# AC-4ch-01.net
KiCad netlist of a schematic drawn in EAGLE
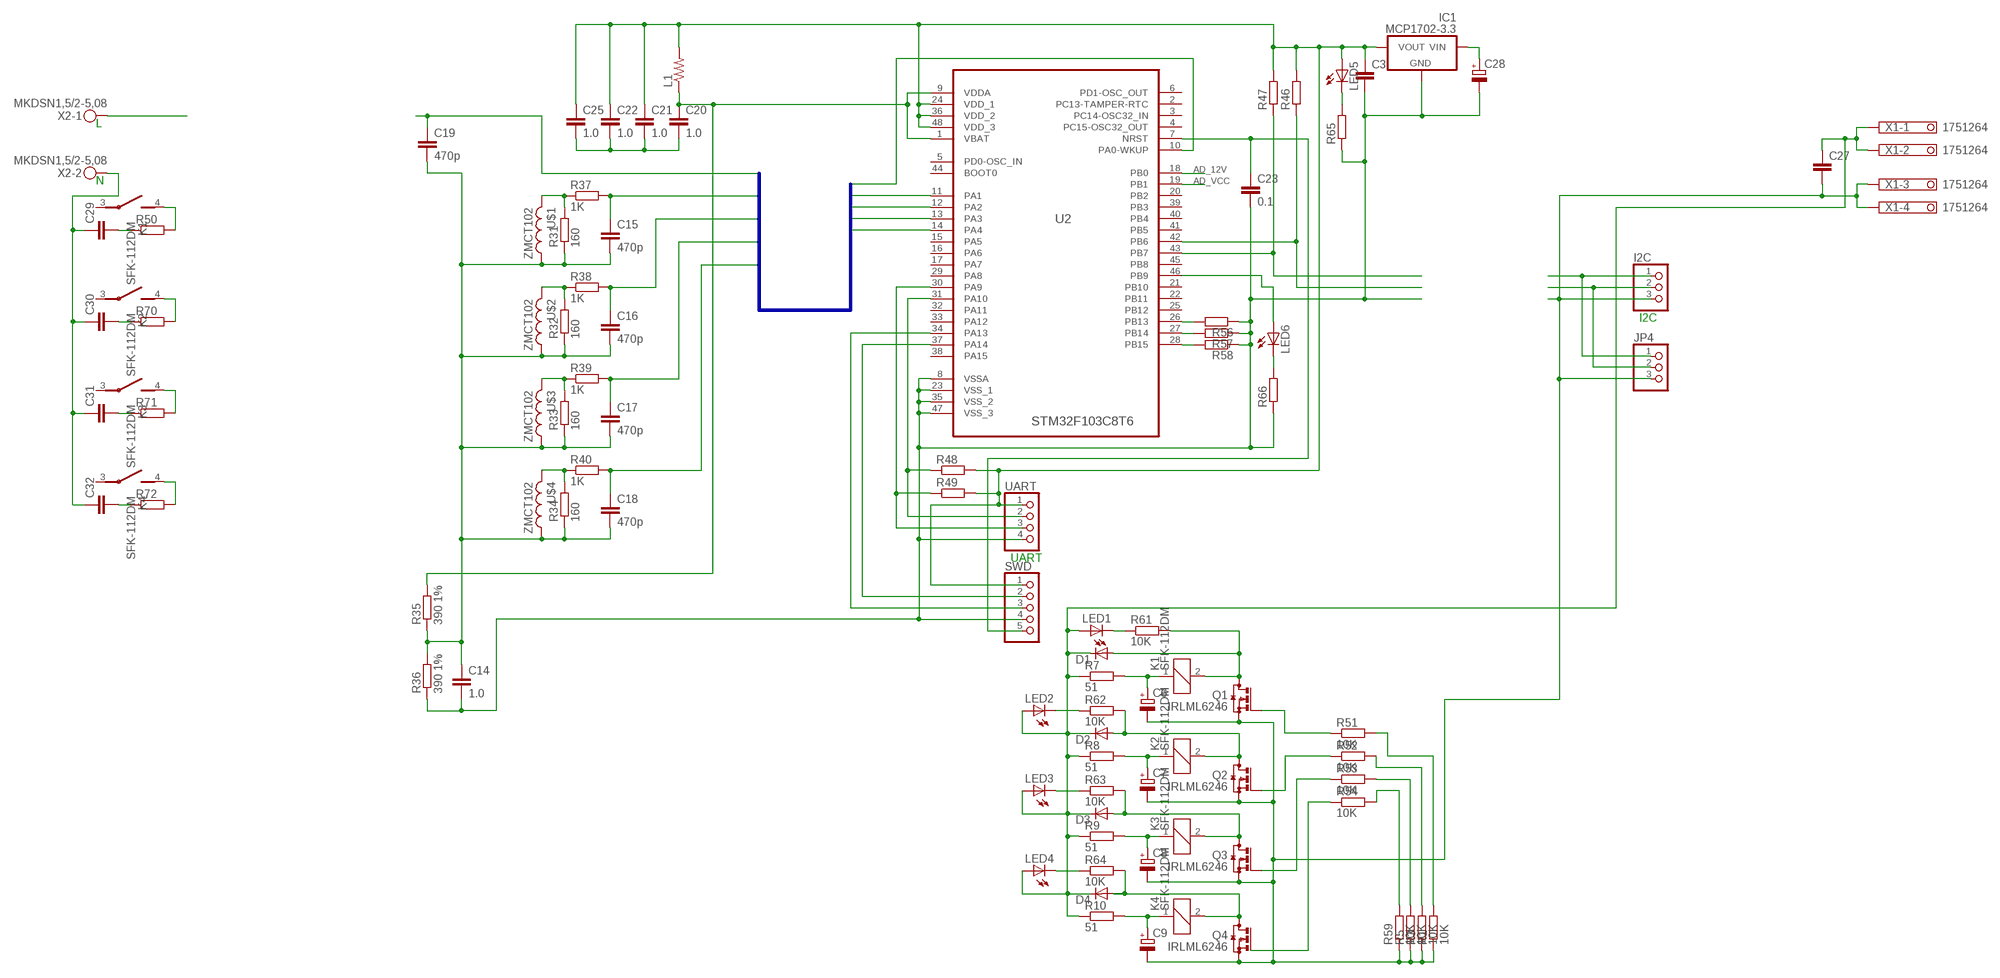
[diagram p0: schematic, sheet 1]

(export (version "E")
  (design (tool "Eeschema 10.0.6"))
  (components
    (comp (ref "C3")
      (value "C-EUC0805")
      (footprint "eagle-import:C0805")
      (libsource (lib "eagle-import") (part "C-EUC0805"))
    )
    (comp (ref "C6")
      (value "CPOL-EUE3.5-8")
      (footprint "eagle-import:E3,5-8")
      (libsource (lib "eagle-import") (part "CPOL-EUE3.5-8"))
    )
    (comp (ref "C7")
      (value "CPOL-EUE3.5-8")
      (footprint "eagle-import:E3,5-8")
      (libsource (lib "eagle-import") (part "CPOL-EUE3.5-8"))
    )
    (comp (ref "C8")
      (value "CPOL-EUE3.5-8")
      (footprint "eagle-import:E3,5-8")
      (libsource (lib "eagle-import") (part "CPOL-EUE3.5-8"))
    )
    (comp (ref "C9")
      (value "CPOL-EUE3.5-8")
      (footprint "eagle-import:E3,5-8")
      (libsource (lib "eagle-import") (part "CPOL-EUE3.5-8"))
    )
    (comp (ref "C14")
      (value "1.0")
      (footprint "eagle-import:C0805")
      (libsource (lib "eagle-import") (part "C-EUC0805"))
    )
    (comp (ref "C15")
      (value "470p")
      (footprint "eagle-import:C0603")
      (libsource (lib "eagle-import") (part "C-EUC0603"))
    )
    (comp (ref "C16")
      (value "470p")
      (footprint "eagle-import:C0603")
      (libsource (lib "eagle-import") (part "C-EUC0603"))
    )
    (comp (ref "C17")
      (value "470p")
      (footprint "eagle-import:C0603")
      (libsource (lib "eagle-import") (part "C-EUC0603"))
    )
    (comp (ref "C18")
      (value "470p")
      (footprint "eagle-import:C0603")
      (libsource (lib "eagle-import") (part "C-EUC0603"))
    )
    (comp (ref "C19")
      (value "470p")
      (footprint "eagle-import:C0603")
      (libsource (lib "eagle-import") (part "C-EUC0603"))
    )
    (comp (ref "C20")
      (value "1.0")
      (footprint "eagle-import:C0805")
      (libsource (lib "eagle-import") (part "C-EUC0805"))
    )
    (comp (ref "C21")
      (value "1.0")
      (footprint "eagle-import:C0805")
      (libsource (lib "eagle-import") (part "C-EUC0805"))
    )
    (comp (ref "C22")
      (value "1.0")
      (footprint "eagle-import:C0805")
      (libsource (lib "eagle-import") (part "C-EUC0805"))
    )
    (comp (ref "C23")
      (value "0.1")
      (footprint "eagle-import:C0603")
      (libsource (lib "eagle-import") (part "C-EUC0603"))
    )
    (comp (ref "C25")
      (value "1.0")
      (footprint "eagle-import:C0805")
      (libsource (lib "eagle-import") (part "C-EUC0805"))
    )
    (comp (ref "C27")
      (value "C-EUC1206")
      (footprint "eagle-import:C1206")
      (libsource (lib "eagle-import") (part "C-EUC1206"))
    )
    (comp (ref "C28")
      (value "CPOL-EUSMCB")
      (footprint "eagle-import:SMC_B")
      (libsource (lib "eagle-import") (part "CPOL-EUSMCB"))
    )
    (comp (ref "C29")
      (value "C-EU225-087X268")
      (footprint "eagle-import:C225-087X268")
      (libsource (lib "eagle-import") (part "C-EU225-087X268"))
    )
    (comp (ref "C30")
      (value "C-EU225-087X268")
      (footprint "eagle-import:C225-087X268")
      (libsource (lib "eagle-import") (part "C-EU225-087X268"))
    )
    (comp (ref "C31")
      (value "C-EU225-087X268")
      (footprint "eagle-import:C225-087X268")
      (libsource (lib "eagle-import") (part "C-EU225-087X268"))
    )
    (comp (ref "C32")
      (value "C-EU225-087X268")
      (footprint "eagle-import:C225-087X268")
      (libsource (lib "eagle-import") (part "C-EU225-087X268"))
    )
    (comp (ref "D1")
      (value "DIODE-SOD123")
      (footprint "eagle-import:SOD123")
      (libsource (lib "eagle-import") (part "DIODE-SOD123"))
    )
    (comp (ref "D2")
      (value "DIODE-SOD123")
      (footprint "eagle-import:SOD123")
      (libsource (lib "eagle-import") (part "DIODE-SOD123"))
    )
    (comp (ref "D3")
      (value "DIODE-SOD123")
      (footprint "eagle-import:SOD123")
      (libsource (lib "eagle-import") (part "DIODE-SOD123"))
    )
    (comp (ref "D4")
      (value "DIODE-SOD123")
      (footprint "eagle-import:SOD123")
      (libsource (lib "eagle-import") (part "DIODE-SOD123"))
    )
    (comp (ref "I2C")
      (value "PINHD-1X3")
      (footprint "eagle-import:1X03")
      (libsource (lib "eagle-import") (part "PINHD-1X3"))
    )
    (comp (ref "IC1")
      (value "MCP1702-3.3")
      (footprint "eagle-import:SOT23-3-ROTATED")
      (libsource (lib "eagle-import") (part "MCP1702SOT23"))
    )
    (comp (ref "JP4")
      (value "PINHD-1X3")
      (footprint "eagle-import:1X03")
      (libsource (lib "eagle-import") (part "PINHD-1X3"))
    )
    (comp (ref "K1")
      (value "SFK-112DM")
      (footprint "eagle-import:SFK112")
      (libsource (lib "eagle-import") (part "SFK-112DM"))
    )
    (comp (ref "K2")
      (value "SFK-112DM")
      (footprint "eagle-import:SFK112")
      (libsource (lib "eagle-import") (part "SFK-112DM"))
    )
    (comp (ref "K3")
      (value "SFK-112DM")
      (footprint "eagle-import:SFK112")
      (libsource (lib "eagle-import") (part "SFK-112DM"))
    )
    (comp (ref "K4")
      (value "SFK-112DM")
      (footprint "eagle-import:SFK112")
      (libsource (lib "eagle-import") (part "SFK-112DM"))
    )
    (comp (ref "L1")
      (value "R-US_M0805")
      (footprint "eagle-import:M0805")
      (libsource (lib "eagle-import") (part "R-US_M0805"))
    )
    (comp (ref "LED1")
      (value "LEDCHIP-LED0805")
      (footprint "eagle-import:CHIP-LED0805")
      (libsource (lib "eagle-import") (part "LEDCHIP-LED0805"))
    )
    (comp (ref "LED2")
      (value "LEDCHIP-LED0805")
      (footprint "eagle-import:CHIP-LED0805")
      (libsource (lib "eagle-import") (part "LEDCHIP-LED0805"))
    )
    (comp (ref "LED3")
      (value "LEDCHIP-LED0805")
      (footprint "eagle-import:CHIP-LED0805")
      (libsource (lib "eagle-import") (part "LEDCHIP-LED0805"))
    )
    (comp (ref "LED4")
      (value "LEDCHIP-LED0805")
      (footprint "eagle-import:CHIP-LED0805")
      (libsource (lib "eagle-import") (part "LEDCHIP-LED0805"))
    )
    (comp (ref "LED5")
      (value "LEDCHIP-LED0805")
      (footprint "eagle-import:CHIP-LED0805")
      (libsource (lib "eagle-import") (part "LEDCHIP-LED0805"))
    )
    (comp (ref "LED6")
      (value "LEDCHIP-LED0805")
      (footprint "eagle-import:CHIP-LED0805")
      (libsource (lib "eagle-import") (part "LEDCHIP-LED0805"))
    )
    (comp (ref "Q1")
      (value "IRLML6246")
      (footprint "eagle-import:SOT23")
      (libsource (lib "eagle-import") (part "BSS123"))
    )
    (comp (ref "Q2")
      (value "IRLML6246")
      (footprint "eagle-import:SOT23")
      (libsource (lib "eagle-import") (part "BSS123"))
    )
    (comp (ref "Q3")
      (value "IRLML6246")
      (footprint "eagle-import:SOT23")
      (libsource (lib "eagle-import") (part "BSS123"))
    )
    (comp (ref "Q4")
      (value "IRLML6246")
      (footprint "eagle-import:SOT23")
      (libsource (lib "eagle-import") (part "BSS123"))
    )
    (comp (ref "R1")
      (value "10K")
      (footprint "eagle-import:R0603")
      (libsource (lib "eagle-import") (part "R-EU_R0603"))
    )
    (comp (ref "R3")
      (value "10K")
      (footprint "eagle-import:R0603")
      (libsource (lib "eagle-import") (part "R-EU_R0603"))
    )
    (comp (ref "R5")
      (value "10K")
      (footprint "eagle-import:R0603")
      (libsource (lib "eagle-import") (part "R-EU_R0603"))
    )
    (comp (ref "R7")
      (value "51")
      (footprint "eagle-import:R1206")
      (libsource (lib "eagle-import") (part "R-EU_R1206"))
    )
    (comp (ref "R8")
      (value "51")
      (footprint "eagle-import:R1206")
      (libsource (lib "eagle-import") (part "R-EU_R1206"))
    )
    (comp (ref "R9")
      (value "51")
      (footprint "eagle-import:R1206")
      (libsource (lib "eagle-import") (part "R-EU_R1206"))
    )
    (comp (ref "R10")
      (value "51")
      (footprint "eagle-import:R1206")
      (libsource (lib "eagle-import") (part "R-EU_R1206"))
    )
    (comp (ref "R31")
      (value "160")
      (footprint "eagle-import:R0603")
      (libsource (lib "eagle-import") (part "R-EU_R0603"))
    )
    (comp (ref "R32")
      (value "160")
      (footprint "eagle-import:R0603")
      (libsource (lib "eagle-import") (part "R-EU_R0603"))
    )
    (comp (ref "R33")
      (value "160")
      (footprint "eagle-import:R0603")
      (libsource (lib "eagle-import") (part "R-EU_R0603"))
    )
    (comp (ref "R34")
      (value "160")
      (footprint "eagle-import:R0603")
      (libsource (lib "eagle-import") (part "R-EU_R0603"))
    )
    (comp (ref "R35")
      (value "390 1%")
      (footprint "eagle-import:R0603")
      (libsource (lib "eagle-import") (part "R-EU_R0603"))
    )
    (comp (ref "R36")
      (value "390 1%")
      (footprint "eagle-import:R0603")
      (libsource (lib "eagle-import") (part "R-EU_R0603"))
    )
    (comp (ref "R37")
      (value "1K")
      (footprint "eagle-import:R0603")
      (libsource (lib "eagle-import") (part "R-EU_R0603"))
    )
    (comp (ref "R38")
      (value "1K")
      (footprint "eagle-import:R0603")
      (libsource (lib "eagle-import") (part "R-EU_R0603"))
    )
    (comp (ref "R39")
      (value "1K")
      (footprint "eagle-import:R0603")
      (libsource (lib "eagle-import") (part "R-EU_R0603"))
    )
    (comp (ref "R40")
      (value "1K")
      (footprint "eagle-import:R0603")
      (libsource (lib "eagle-import") (part "R-EU_R0603"))
    )
    (comp (ref "R46")
      (value "R-EU_R0603")
      (footprint "eagle-import:R0603")
      (libsource (lib "eagle-import") (part "R-EU_R0603"))
    )
    (comp (ref "R47")
      (value "R-EU_R0603")
      (footprint "eagle-import:R0603")
      (libsource (lib "eagle-import") (part "R-EU_R0603"))
    )
    (comp (ref "R48")
      (value "R-EU_R0603")
      (footprint "eagle-import:R0603")
      (libsource (lib "eagle-import") (part "R-EU_R0603"))
    )
    (comp (ref "R49")
      (value "R-EU_R0603")
      (footprint "eagle-import:R0603")
      (libsource (lib "eagle-import") (part "R-EU_R0603"))
    )
    (comp (ref "R50")
      (value "R-EU_0414/5V")
      (footprint "eagle-import:0414V")
      (libsource (lib "eagle-import") (part "R-EU_0414/5V"))
    )
    (comp (ref "R51")
      (value "10K")
      (footprint "eagle-import:R0603")
      (libsource (lib "eagle-import") (part "R-EU_R0603"))
    )
    (comp (ref "R52")
      (value "10K")
      (footprint "eagle-import:R0603")
      (libsource (lib "eagle-import") (part "R-EU_R0603"))
    )
    (comp (ref "R53")
      (value "10K")
      (footprint "eagle-import:R0603")
      (libsource (lib "eagle-import") (part "R-EU_R0603"))
    )
    (comp (ref "R54")
      (value "10K")
      (footprint "eagle-import:R0603")
      (libsource (lib "eagle-import") (part "R-EU_R0603"))
    )
    (comp (ref "R56")
      (value "R-EU_R0603")
      (footprint "eagle-import:R0603")
      (libsource (lib "eagle-import") (part "R-EU_R0603"))
    )
    (comp (ref "R57")
      (value "R-EU_R0603")
      (footprint "eagle-import:R0603")
      (libsource (lib "eagle-import") (part "R-EU_R0603"))
    )
    (comp (ref "R58")
      (value "R-EU_R0603")
      (footprint "eagle-import:R0603")
      (libsource (lib "eagle-import") (part "R-EU_R0603"))
    )
    (comp (ref "R59")
      (value "10K")
      (footprint "eagle-import:R0603")
      (libsource (lib "eagle-import") (part "R-EU_R0603"))
    )
    (comp (ref "R61")
      (value "10K")
      (footprint "eagle-import:R0603")
      (libsource (lib "eagle-import") (part "R-EU_R0603"))
    )
    (comp (ref "R62")
      (value "10K")
      (footprint "eagle-import:R0603")
      (libsource (lib "eagle-import") (part "R-EU_R0603"))
    )
    (comp (ref "R63")
      (value "10K")
      (footprint "eagle-import:R0603")
      (libsource (lib "eagle-import") (part "R-EU_R0603"))
    )
    (comp (ref "R64")
      (value "10K")
      (footprint "eagle-import:R0603")
      (libsource (lib "eagle-import") (part "R-EU_R0603"))
    )
    (comp (ref "R65")
      (value "R-EU_R0603")
      (footprint "eagle-import:R0603")
      (libsource (lib "eagle-import") (part "R-EU_R0603"))
    )
    (comp (ref "R66")
      (value "R-EU_R0603")
      (footprint "eagle-import:R0603")
      (libsource (lib "eagle-import") (part "R-EU_R0603"))
    )
    (comp (ref "R70")
      (value "R-EU_0414/5V")
      (footprint "eagle-import:0414V")
      (libsource (lib "eagle-import") (part "R-EU_0414/5V"))
    )
    (comp (ref "R71")
      (value "R-EU_0414/5V")
      (footprint "eagle-import:0414V")
      (libsource (lib "eagle-import") (part "R-EU_0414/5V"))
    )
    (comp (ref "R72")
      (value "R-EU_0414/5V")
      (footprint "eagle-import:0414V")
      (libsource (lib "eagle-import") (part "R-EU_0414/5V"))
    )
    (comp (ref "SWD")
      (value "PINHD-1X5")
      (footprint "eagle-import:1X05")
      (libsource (lib "eagle-import") (part "PINHD-1X5"))
    )
    (comp (ref "U$1")
      (value "ZMCT102")
      (footprint "eagle-import:ZMCT")
      (libsource (lib "eagle-import") (part "ZMCT102"))
    )
    (comp (ref "U$2")
      (value "ZMCT102")
      (footprint "eagle-import:ZMCT")
      (libsource (lib "eagle-import") (part "ZMCT102"))
    )
    (comp (ref "U$3")
      (value "ZMCT102")
      (footprint "eagle-import:ZMCT")
      (libsource (lib "eagle-import") (part "ZMCT102"))
    )
    (comp (ref "U$4")
      (value "ZMCT102")
      (footprint "eagle-import:ZMCT")
      (libsource (lib "eagle-import") (part "ZMCT102"))
    )
    (comp (ref "U2")
      (value "STM32F103C8T6")
      (footprint "eagle-import:QFP50P900X900X160-48N")
      (fields (field (name "MPN") "STM32F100CBT6B"))
      (libsource (lib "eagle-import") (part "STM32F100CBT6B"))
    )
    (comp (ref "UART")
      (value "PINHD-1X4")
      (footprint "eagle-import:1X04")
      (libsource (lib "eagle-import") (part "PINHD-1X4"))
    )
    (comp (ref "X1")
      (value "1751264")
      (footprint "eagle-import:1751264")
      (libsource (lib "eagle-import") (part "1751264"))
    )
    (comp (ref "X2")
      (value "MKDSN1,5/2-5,08")
      (footprint "eagle-import:MKDSN1,5_2-5,08")
      (libsource (lib "eagle-import") (part "MKDSN1,5/2-5,08"))
    )
  )
  (nets
    (net (code "1") (name "/0V") (class "Default")
      (node (ref "C14") (pin "2") (pinfunction "2_2") (pintype "passive"))
      (node (ref "C20") (pin "2") (pinfunction "2_2") (pintype "passive"))
      (node (ref "C21") (pin "2") (pinfunction "2_2") (pintype "passive"))
      (node (ref "C22") (pin "2") (pinfunction "2_2") (pintype "passive"))
      (node (ref "C23") (pin "2") (pinfunction "2_2") (pintype "passive"))
      (node (ref "C25") (pin "2") (pinfunction "2_2") (pintype "passive"))
      (node (ref "C28") (pin "-") (pinfunction "-_-") (pintype "passive"))
      (node (ref "C3") (pin "2") (pinfunction "2_2") (pintype "passive"))
      (node (ref "IC1") (pin "1") (pinfunction "GND_1") (pintype "passive"))
      (node (ref "R36") (pin "1") (pinfunction "1_1") (pintype "passive"))
      (node (ref "R56") (pin "1") (pinfunction "1_1") (pintype "passive"))
      (node (ref "R57") (pin "1") (pinfunction "1_1") (pintype "passive"))
      (node (ref "R58") (pin "1") (pinfunction "1_1") (pintype "passive"))
      (node (ref "R65") (pin "1") (pinfunction "1_1") (pintype "passive"))
      (node (ref "R66") (pin "1") (pinfunction "1_1") (pintype "passive"))
      (node (ref "SWD") (pin "4") (pinfunction "4_4") (pintype "passive"))
      (node (ref "U2") (pin "23") (pinfunction "VSS_1_23") (pintype "power_in"))
      (node (ref "U2") (pin "35") (pinfunction "VSS_2_35") (pintype "power_in"))
      (node (ref "U2") (pin "47") (pinfunction "VSS_3_47") (pintype "power_in"))
      (node (ref "U2") (pin "8") (pinfunction "VSSA_8") (pintype "power_in"))
      (node (ref "UART") (pin "4") (pinfunction "4_4") (pintype "passive"))
    )
    (net (code "2") (name "/A0") (class "Default")
      (node (ref "C18") (pin "1") (pinfunction "1_1") (pintype "passive"))
      (node (ref "R40") (pin "2") (pinfunction "2_2") (pintype "passive"))
      (node (ref "U2") (pin "10") (pinfunction "PA0-WKUP_10") (pintype "bidirectional"))
    )
    (net (code "3") (name "/A1") (class "Default")
      (node (ref "C17") (pin "1") (pinfunction "1_1") (pintype "passive"))
      (node (ref "R39") (pin "2") (pinfunction "2_2") (pintype "passive"))
      (node (ref "U2") (pin "11") (pinfunction "PA1_11") (pintype "bidirectional"))
    )
    (net (code "4") (name "/A2") (class "Default")
      (node (ref "C16") (pin "1") (pinfunction "1_1") (pintype "passive"))
      (node (ref "R38") (pin "2") (pinfunction "2_2") (pintype "passive"))
      (node (ref "U2") (pin "12") (pinfunction "PA2_12") (pintype "bidirectional"))
    )
    (net (code "5") (name "/A3") (class "Default")
      (node (ref "C15") (pin "1") (pinfunction "1_1") (pintype "passive"))
      (node (ref "R37") (pin "2") (pinfunction "2_2") (pintype "passive"))
      (node (ref "U2") (pin "13") (pinfunction "PA3_13") (pintype "bidirectional"))
    )
    (net (code "6") (name "/A4") (class "Default")
      (node (ref "C19") (pin "1") (pinfunction "1_1") (pintype "passive"))
      (node (ref "U2") (pin "14") (pinfunction "PA4_14") (pintype "bidirectional"))
    )
    (net (code "7") (name "/AD_12V") (class "Default")
      (node (ref "U2") (pin "18") (pinfunction "PB0_18") (pintype "bidirectional"))
    )
    (net (code "8") (name "/AD_VCC") (class "Default")
      (node (ref "U2") (pin "19") (pinfunction "PB1_19") (pintype "bidirectional"))
    )
    (net (code "9") (name "Net-(C6-Pad+)") (class "Default")
      (node (ref "C6") (pin "+") (pinfunction "+_+") (pintype "passive"))
      (node (ref "K1") (pin "1") (pinfunction "1_1") (pintype "passive"))
      (node (ref "R7") (pin "2") (pinfunction "2_2") (pintype "passive"))
    )
    (net (code "10") (name "Net-(C7-Pad+)") (class "Default")
      (node (ref "C7") (pin "+") (pinfunction "+_+") (pintype "passive"))
      (node (ref "K2") (pin "1") (pinfunction "1_1") (pintype "passive"))
      (node (ref "R8") (pin "2") (pinfunction "2_2") (pintype "passive"))
    )
    (net (code "11") (name "Net-(C8-Pad+)") (class "Default")
      (node (ref "C8") (pin "+") (pinfunction "+_+") (pintype "passive"))
      (node (ref "K3") (pin "1") (pinfunction "1_1") (pintype "passive"))
      (node (ref "R9") (pin "2") (pinfunction "2_2") (pintype "passive"))
    )
    (net (code "12") (name "Net-(C9-Pad+)") (class "Default")
      (node (ref "C9") (pin "+") (pinfunction "+_+") (pintype "passive"))
      (node (ref "K4") (pin "1") (pinfunction "1_1") (pintype "passive"))
      (node (ref "R10") (pin "2") (pinfunction "2_2") (pintype "passive"))
    )
    (net (code "13") (name "Net-(C14-Pad1)") (class "Default")
      (node (ref "C14") (pin "1") (pinfunction "1_1") (pintype "passive"))
      (node (ref "C15") (pin "2") (pinfunction "2_2") (pintype "passive"))
      (node (ref "C16") (pin "2") (pinfunction "2_2") (pintype "passive"))
      (node (ref "C17") (pin "2") (pinfunction "2_2") (pintype "passive"))
      (node (ref "C18") (pin "2") (pinfunction "2_2") (pintype "passive"))
      (node (ref "C19") (pin "2") (pinfunction "2_2") (pintype "passive"))
      (node (ref "R31") (pin "1") (pinfunction "1_1") (pintype "passive"))
      (node (ref "R32") (pin "1") (pinfunction "1_1") (pintype "passive"))
      (node (ref "R33") (pin "1") (pinfunction "1_1") (pintype "passive"))
      (node (ref "R34") (pin "1") (pinfunction "1_1") (pintype "passive"))
      (node (ref "R35") (pin "1") (pinfunction "1_1") (pintype "passive"))
      (node (ref "R36") (pin "2") (pinfunction "2_2") (pintype "passive"))
      (node (ref "U$1") (pin "1") (pinfunction "1_1") (pintype "passive"))
      (node (ref "U$2") (pin "1") (pinfunction "1_1") (pintype "passive"))
      (node (ref "U$3") (pin "1") (pinfunction "1_1") (pintype "passive"))
      (node (ref "U$4") (pin "1") (pinfunction "1_1") (pintype "passive"))
    )
    (net (code "14") (name "Net-(C29-Pad2)") (class "Default")
      (node (ref "C29") (pin "2") (pinfunction "2_2") (pintype "passive"))
      (node (ref "R50") (pin "1") (pinfunction "1_1") (pintype "passive"))
    )
    (net (code "15") (name "Net-(C30-Pad2)") (class "Default")
      (node (ref "C30") (pin "2") (pinfunction "2_2") (pintype "passive"))
      (node (ref "R70") (pin "1") (pinfunction "1_1") (pintype "passive"))
    )
    (net (code "16") (name "Net-(C31-Pad2)") (class "Default")
      (node (ref "C31") (pin "2") (pinfunction "2_2") (pintype "passive"))
      (node (ref "R71") (pin "1") (pinfunction "1_1") (pintype "passive"))
    )
    (net (code "17") (name "Net-(C32-Pad2)") (class "Default")
      (node (ref "C32") (pin "2") (pinfunction "2_2") (pintype "passive"))
      (node (ref "R72") (pin "1") (pinfunction "1_1") (pintype "passive"))
    )
    (net (code "18") (name "Net-(I2C-Pad1)") (class "Default")
      (node (ref "I2C") (pin "1") (pinfunction "1_1") (pintype "passive"))
      (node (ref "JP4") (pin "1") (pinfunction "1_1") (pintype "passive"))
    )
    (net (code "19") (name "Net-(I2C-Pad2)") (class "Default")
      (node (ref "I2C") (pin "2") (pinfunction "2_2") (pintype "passive"))
      (node (ref "JP4") (pin "2") (pinfunction "2_2") (pintype "passive"))
    )
    (net (code "20") (name "Net-(IC1-VIN)") (class "Default")
      (node (ref "C28") (pin "+") (pinfunction "+_+") (pintype "passive"))
      (node (ref "IC1") (pin "3") (pinfunction "VIN_3") (pintype "input"))
    )
    (net (code "21") (name "Net-(IC1-VOUT)") (class "Default")
      (node (ref "C21") (pin "1") (pinfunction "1_1") (pintype "passive"))
      (node (ref "C22") (pin "1") (pinfunction "1_1") (pintype "passive"))
      (node (ref "C25") (pin "1") (pinfunction "1_1") (pintype "passive"))
      (node (ref "C3") (pin "1") (pinfunction "1_1") (pintype "passive"))
      (node (ref "IC1") (pin "2") (pinfunction "VOUT_2") (pintype "passive"))
      (node (ref "L1") (pin "2") (pinfunction "2_2") (pintype "passive"))
      (node (ref "LED5") (pin "A") (pinfunction "A_A") (pintype "passive"))
      (node (ref "R46") (pin "2") (pinfunction "2_2") (pintype "passive"))
      (node (ref "R47") (pin "2") (pinfunction "2_2") (pintype "passive"))
      (node (ref "R48") (pin "2") (pinfunction "2_2") (pintype "passive"))
      (node (ref "R49") (pin "2") (pinfunction "2_2") (pintype "passive"))
      (node (ref "SWD") (pin "1") (pinfunction "1_1") (pintype "passive"))
      (node (ref "U2") (pin "24") (pinfunction "VDD_1_24") (pintype "power_in"))
      (node (ref "U2") (pin "36") (pinfunction "VDD_2_36") (pintype "power_in"))
      (node (ref "U2") (pin "48") (pinfunction "VDD_3_48") (pintype "power_in"))
      (node (ref "UART") (pin "1") (pinfunction "1_1") (pintype "passive"))
    )
    (net (code "22") (name "Net-(K1A-S)") (class "Default")
      (node (ref "K1") (pin "4") (pinfunction "S_4") (pintype "passive"))
      (node (ref "R50") (pin "2") (pinfunction "2_2") (pintype "passive"))
    )
    (net (code "23") (name "Net-(K2A-S)") (class "Default")
      (node (ref "K2") (pin "4") (pinfunction "S_4") (pintype "passive"))
      (node (ref "R70") (pin "2") (pinfunction "2_2") (pintype "passive"))
    )
    (net (code "24") (name "Net-(K3A-S)") (class "Default")
      (node (ref "K3") (pin "4") (pinfunction "S_4") (pintype "passive"))
      (node (ref "R71") (pin "2") (pinfunction "2_2") (pintype "passive"))
    )
    (net (code "25") (name "Net-(K4A-S)") (class "Default")
      (node (ref "K4") (pin "4") (pinfunction "S_4") (pintype "passive"))
      (node (ref "R72") (pin "2") (pinfunction "2_2") (pintype "passive"))
    )
    (net (code "26") (name "Net-(LED1-PadC)") (class "Default")
      (node (ref "LED1") (pin "C") (pinfunction "C_C") (pintype "passive"))
      (node (ref "R61") (pin "1") (pinfunction "1_1") (pintype "passive"))
    )
    (net (code "27") (name "Net-(LED2-PadC)") (class "Default")
      (node (ref "LED2") (pin "C") (pinfunction "C_C") (pintype "passive"))
      (node (ref "R62") (pin "1") (pinfunction "1_1") (pintype "passive"))
    )
    (net (code "28") (name "Net-(LED3-PadC)") (class "Default")
      (node (ref "LED3") (pin "C") (pinfunction "C_C") (pintype "passive"))
      (node (ref "R63") (pin "1") (pinfunction "1_1") (pintype "passive"))
    )
    (net (code "29") (name "Net-(LED4-PadC)") (class "Default")
      (node (ref "LED4") (pin "C") (pinfunction "C_C") (pintype "passive"))
      (node (ref "R64") (pin "1") (pinfunction "1_1") (pintype "passive"))
    )
    (net (code "30") (name "Net-(LED5-PadC)") (class "Default")
      (node (ref "LED5") (pin "C") (pinfunction "C_C") (pintype "passive"))
      (node (ref "R65") (pin "2") (pinfunction "2_2") (pintype "passive"))
    )
    (net (code "31") (name "Net-(LED6-PadC)") (class "Default")
      (node (ref "LED6") (pin "C") (pinfunction "C_C") (pintype "passive"))
      (node (ref "R66") (pin "2") (pinfunction "2_2") (pintype "passive"))
    )
    (net (code "32") (name "Net-(Q1-D)") (class "Default")
      (node (ref "D1") (pin "A") (pinfunction "A_A") (pintype "passive"))
      (node (ref "K1") (pin "2") (pinfunction "2_2") (pintype "passive"))
      (node (ref "Q1") (pin "3") (pinfunction "D_3") (pintype "passive"))
      (node (ref "R61") (pin "2") (pinfunction "2_2") (pintype "passive"))
    )
    (net (code "33") (name "Net-(Q1-G)") (class "Default")
      (node (ref "Q1") (pin "1") (pinfunction "G_1") (pintype "passive"))
      (node (ref "R51") (pin "1") (pinfunction "1_1") (pintype "passive"))
    )
    (net (code "34") (name "Net-(Q1-S)") (class "Default")
      (node (ref "C27") (pin "2") (pinfunction "2_2") (pintype "passive"))
      (node (ref "C6") (pin "-") (pinfunction "-_-") (pintype "passive"))
      (node (ref "C7") (pin "-") (pinfunction "-_-") (pintype "passive"))
      (node (ref "C8") (pin "-") (pinfunction "-_-") (pintype "passive"))
      (node (ref "C9") (pin "-") (pinfunction "-_-") (pintype "passive"))
      (node (ref "I2C") (pin "3") (pinfunction "3_3") (pintype "passive"))
      (node (ref "JP4") (pin "3") (pinfunction "3_3") (pintype "passive"))
      (node (ref "Q1") (pin "2") (pinfunction "S_2") (pintype "passive"))
      (node (ref "Q2") (pin "2") (pinfunction "S_2") (pintype "passive"))
      (node (ref "Q3") (pin "2") (pinfunction "S_2") (pintype "passive"))
      (node (ref "Q4") (pin "2") (pinfunction "S_2") (pintype "passive"))
      (node (ref "R1") (pin "1") (pinfunction "1_1") (pintype "passive"))
      (node (ref "R3") (pin "1") (pinfunction "1_1") (pintype "passive"))
      (node (ref "R5") (pin "1") (pinfunction "1_1") (pintype "passive"))
      (node (ref "R59") (pin "1") (pinfunction "1_1") (pintype "passive"))
      (node (ref "X1") (pin "3") (pinfunction "K_3") (pintype "passive"))
      (node (ref "X1") (pin "4") (pinfunction "K_4") (pintype "passive"))
    )
    (net (code "35") (name "Net-(Q2-D)") (class "Default")
      (node (ref "D2") (pin "A") (pinfunction "A_A") (pintype "passive"))
      (node (ref "K2") (pin "2") (pinfunction "2_2") (pintype "passive"))
      (node (ref "Q2") (pin "3") (pinfunction "D_3") (pintype "passive"))
      (node (ref "R62") (pin "2") (pinfunction "2_2") (pintype "passive"))
    )
    (net (code "36") (name "Net-(Q2-G)") (class "Default")
      (node (ref "Q2") (pin "1") (pinfunction "G_1") (pintype "passive"))
      (node (ref "R52") (pin "1") (pinfunction "1_1") (pintype "passive"))
    )
    (net (code "37") (name "Net-(Q3-D)") (class "Default")
      (node (ref "D3") (pin "A") (pinfunction "A_A") (pintype "passive"))
      (node (ref "K3") (pin "2") (pinfunction "2_2") (pintype "passive"))
      (node (ref "Q3") (pin "3") (pinfunction "D_3") (pintype "passive"))
      (node (ref "R63") (pin "2") (pinfunction "2_2") (pintype "passive"))
    )
    (net (code "38") (name "Net-(Q3-G)") (class "Default")
      (node (ref "Q3") (pin "1") (pinfunction "G_1") (pintype "passive"))
      (node (ref "R53") (pin "1") (pinfunction "1_1") (pintype "passive"))
    )
    (net (code "39") (name "Net-(Q4-D)") (class "Default")
      (node (ref "D4") (pin "A") (pinfunction "A_A") (pintype "passive"))
      (node (ref "K4") (pin "2") (pinfunction "2_2") (pintype "passive"))
      (node (ref "Q4") (pin "3") (pinfunction "D_3") (pintype "passive"))
      (node (ref "R64") (pin "2") (pinfunction "2_2") (pintype "passive"))
    )
    (net (code "40") (name "Net-(Q4-G)") (class "Default")
      (node (ref "Q4") (pin "1") (pinfunction "G_1") (pintype "passive"))
      (node (ref "R54") (pin "1") (pinfunction "1_1") (pintype "passive"))
    )
    (net (code "41") (name "Net-(R1-Pad2)") (class "Default")
      (node (ref "R1") (pin "2") (pinfunction "2_2") (pintype "passive"))
      (node (ref "R51") (pin "2") (pinfunction "2_2") (pintype "passive"))
    )
    (net (code "42") (name "Net-(R3-Pad2)") (class "Default")
      (node (ref "R3") (pin "2") (pinfunction "2_2") (pintype "passive"))
      (node (ref "R52") (pin "2") (pinfunction "2_2") (pintype "passive"))
    )
    (net (code "43") (name "Net-(R5-Pad2)") (class "Default")
      (node (ref "R5") (pin "2") (pinfunction "2_2") (pintype "passive"))
      (node (ref "R53") (pin "2") (pinfunction "2_2") (pintype "passive"))
    )
    (net (code "44") (name "Net-(R31-Pad2)") (class "Default")
      (node (ref "R31") (pin "2") (pinfunction "2_2") (pintype "passive"))
      (node (ref "R37") (pin "1") (pinfunction "1_1") (pintype "passive"))
      (node (ref "U$1") (pin "2") (pinfunction "2_2") (pintype "passive"))
    )
    (net (code "45") (name "Net-(R32-Pad2)") (class "Default")
      (node (ref "R32") (pin "2") (pinfunction "2_2") (pintype "passive"))
      (node (ref "R38") (pin "1") (pinfunction "1_1") (pintype "passive"))
      (node (ref "U$2") (pin "2") (pinfunction "2_2") (pintype "passive"))
    )
    (net (code "46") (name "Net-(R33-Pad2)") (class "Default")
      (node (ref "R33") (pin "2") (pinfunction "2_2") (pintype "passive"))
      (node (ref "R39") (pin "1") (pinfunction "1_1") (pintype "passive"))
      (node (ref "U$3") (pin "2") (pinfunction "2_2") (pintype "passive"))
    )
    (net (code "47") (name "Net-(R34-Pad2)") (class "Default")
      (node (ref "R34") (pin "2") (pinfunction "2_2") (pintype "passive"))
      (node (ref "R40") (pin "1") (pinfunction "1_1") (pintype "passive"))
      (node (ref "U$4") (pin "2") (pinfunction "2_2") (pintype "passive"))
    )
    (net (code "48") (name "Net-(R54-Pad2)") (class "Default")
      (node (ref "R54") (pin "2") (pinfunction "2_2") (pintype "passive"))
      (node (ref "R59") (pin "2") (pinfunction "2_2") (pintype "passive"))
    )
    (net (code "49") (name "Net-(U2-NRST)") (class "Default")
      (node (ref "C23") (pin "1") (pinfunction "1_1") (pintype "passive"))
      (node (ref "SWD") (pin "5") (pinfunction "5_5") (pintype "passive"))
      (node (ref "U2") (pin "7") (pinfunction "NRST_7") (pintype "bidirectional"))
    )
    (net (code "50") (name "Net-(U2-PA9)") (class "Default")
      (node (ref "R49") (pin "1") (pinfunction "1_1") (pintype "passive"))
      (node (ref "U2") (pin "30") (pinfunction "PA9_30") (pintype "bidirectional"))
      (node (ref "UART") (pin "3") (pinfunction "3_3") (pintype "passive"))
    )
    (net (code "51") (name "Net-(U2-PA10)") (class "Default")
      (node (ref "R48") (pin "1") (pinfunction "1_1") (pintype "passive"))
      (node (ref "U2") (pin "31") (pinfunction "PA10_31") (pintype "bidirectional"))
      (node (ref "UART") (pin "2") (pinfunction "2_2") (pintype "passive"))
    )
    (net (code "52") (name "Net-(U2-PA13)") (class "Default")
      (node (ref "SWD") (pin "3") (pinfunction "3_3") (pintype "passive"))
      (node (ref "U2") (pin "34") (pinfunction "PA13_34") (pintype "bidirectional"))
    )
    (net (code "53") (name "Net-(U2-PA14)") (class "Default")
      (node (ref "SWD") (pin "2") (pinfunction "2_2") (pintype "passive"))
      (node (ref "U2") (pin "37") (pinfunction "PA14_37") (pintype "bidirectional"))
    )
    (net (code "54") (name "Net-(U2-PB6)") (class "Default")
      (node (ref "R46") (pin "1") (pinfunction "1_1") (pintype "passive"))
      (node (ref "U2") (pin "42") (pinfunction "PB6_42") (pintype "bidirectional"))
    )
    (net (code "55") (name "Net-(U2-PB7)") (class "Default")
      (node (ref "R47") (pin "1") (pinfunction "1_1") (pintype "passive"))
      (node (ref "U2") (pin "43") (pinfunction "PB7_43") (pintype "bidirectional"))
    )
    (net (code "56") (name "Net-(U2-PB9)") (class "Default")
      (node (ref "LED6") (pin "A") (pinfunction "A_A") (pintype "passive"))
      (node (ref "U2") (pin "46") (pinfunction "PB9_46") (pintype "bidirectional"))
    )
    (net (code "57") (name "Net-(U2-PB13)") (class "Default")
      (node (ref "R56") (pin "2") (pinfunction "2_2") (pintype "passive"))
      (node (ref "U2") (pin "26") (pinfunction "PB13_26") (pintype "bidirectional"))
    )
    (net (code "58") (name "Net-(U2-PB14)") (class "Default")
      (node (ref "R57") (pin "2") (pinfunction "2_2") (pintype "passive"))
      (node (ref "U2") (pin "27") (pinfunction "PB14_27") (pintype "bidirectional"))
    )
    (net (code "59") (name "Net-(U2-PB15)") (class "Default")
      (node (ref "R58") (pin "2") (pinfunction "2_2") (pintype "passive"))
      (node (ref "U2") (pin "28") (pinfunction "PB15_28") (pintype "bidirectional"))
    )
    (net (code "60") (name "Net-(U2-VBAT)") (class "Default")
      (node (ref "C20") (pin "1") (pinfunction "1_1") (pintype "passive"))
      (node (ref "L1") (pin "1") (pinfunction "1_1") (pintype "passive"))
      (node (ref "R35") (pin "2") (pinfunction "2_2") (pintype "passive"))
      (node (ref "U2") (pin "1") (pinfunction "VBAT_1") (pintype "power_in"))
      (node (ref "U2") (pin "9") (pinfunction "VDDA_9") (pintype "power_in"))
    )
    (net (code "61") (name "Net-(X1A-K)") (class "Default")
      (node (ref "C27") (pin "1") (pinfunction "1_1") (pintype "passive"))
      (node (ref "D1") (pin "C") (pinfunction "C_C") (pintype "passive"))
      (node (ref "D2") (pin "C") (pinfunction "C_C") (pintype "passive"))
      (node (ref "D3") (pin "C") (pinfunction "C_C") (pintype "passive"))
      (node (ref "D4") (pin "C") (pinfunction "C_C") (pintype "passive"))
      (node (ref "LED1") (pin "A") (pinfunction "A_A") (pintype "passive"))
      (node (ref "LED2") (pin "A") (pinfunction "A_A") (pintype "passive"))
      (node (ref "LED3") (pin "A") (pinfunction "A_A") (pintype "passive"))
      (node (ref "LED4") (pin "A") (pinfunction "A_A") (pintype "passive"))
      (node (ref "R10") (pin "1") (pinfunction "1_1") (pintype "passive"))
      (node (ref "R7") (pin "1") (pinfunction "1_1") (pintype "passive"))
      (node (ref "R8") (pin "1") (pinfunction "1_1") (pintype "passive"))
      (node (ref "R9") (pin "1") (pinfunction "1_1") (pintype "passive"))
      (node (ref "X1") (pin "1") (pinfunction "K_1") (pintype "passive"))
      (node (ref "X1") (pin "2") (pinfunction "K_2") (pintype "passive"))
    )
    (net (code "62") (name "Net-(X2B-KL)") (class "Default")
      (node (ref "C29") (pin "1") (pinfunction "1_1") (pintype "passive"))
      (node (ref "C30") (pin "1") (pinfunction "1_1") (pintype "passive"))
      (node (ref "C31") (pin "1") (pinfunction "1_1") (pintype "passive"))
      (node (ref "C32") (pin "1") (pinfunction "1_1") (pintype "passive"))
      (node (ref "X2") (pin "2") (pinfunction "KL_2") (pintype "passive"))
    )
    (net (code "63") (name "unconnected-(K1A-P-Pad3)") (class "Default")
      (node (ref "K1") (pin "3") (pinfunction "P_3") (pintype "passive"))
    )
    (net (code "64") (name "unconnected-(K2A-P-Pad3)") (class "Default")
      (node (ref "K2") (pin "3") (pinfunction "P_3") (pintype "passive"))
    )
    (net (code "65") (name "unconnected-(K3A-P-Pad3)") (class "Default")
      (node (ref "K3") (pin "3") (pinfunction "P_3") (pintype "passive"))
    )
    (net (code "66") (name "unconnected-(K4A-P-Pad3)") (class "Default")
      (node (ref "K4") (pin "3") (pinfunction "P_3") (pintype "passive"))
    )
    (net (code "67") (name "unconnected-(U2-BOOT0-Pad44)") (class "Default")
      (node (ref "U2") (pin "44") (pinfunction "BOOT0_44") (pintype "input"))
    )
    (net (code "68") (name "unconnected-(U2-PA5-Pad15)") (class "Default")
      (node (ref "U2") (pin "15") (pinfunction "PA5_15") (pintype "bidirectional"))
    )
    (net (code "69") (name "unconnected-(U2-PA6-Pad16)") (class "Default")
      (node (ref "U2") (pin "16") (pinfunction "PA6_16") (pintype "bidirectional"))
    )
    (net (code "70") (name "unconnected-(U2-PA7-Pad17)") (class "Default")
      (node (ref "U2") (pin "17") (pinfunction "PA7_17") (pintype "bidirectional"))
    )
    (net (code "71") (name "unconnected-(U2-PA8-Pad29)") (class "Default")
      (node (ref "U2") (pin "29") (pinfunction "PA8_29") (pintype "bidirectional"))
    )
    (net (code "72") (name "unconnected-(U2-PA11-Pad32)") (class "Default")
      (node (ref "U2") (pin "32") (pinfunction "PA11_32") (pintype "bidirectional"))
    )
    (net (code "73") (name "unconnected-(U2-PA12-Pad33)") (class "Default")
      (node (ref "U2") (pin "33") (pinfunction "PA12_33") (pintype "bidirectional"))
    )
    (net (code "74") (name "unconnected-(U2-PA15-Pad38)") (class "Default")
      (node (ref "U2") (pin "38") (pinfunction "PA15_38") (pintype "bidirectional"))
    )
    (net (code "75") (name "unconnected-(U2-PB2-Pad20)") (class "Default")
      (node (ref "U2") (pin "20") (pinfunction "PB2_20") (pintype "bidirectional"))
    )
    (net (code "76") (name "unconnected-(U2-PB3-Pad39)") (class "Default")
      (node (ref "U2") (pin "39") (pinfunction "PB3_39") (pintype "bidirectional"))
    )
    (net (code "77") (name "unconnected-(U2-PB4-Pad40)") (class "Default")
      (node (ref "U2") (pin "40") (pinfunction "PB4_40") (pintype "bidirectional"))
    )
    (net (code "78") (name "unconnected-(U2-PB5-Pad41)") (class "Default")
      (node (ref "U2") (pin "41") (pinfunction "PB5_41") (pintype "bidirectional"))
    )
    (net (code "79") (name "unconnected-(U2-PB8-Pad45)") (class "Default")
      (node (ref "U2") (pin "45") (pinfunction "PB8_45") (pintype "bidirectional"))
    )
    (net (code "80") (name "unconnected-(U2-PB10-Pad21)") (class "Default")
      (node (ref "U2") (pin "21") (pinfunction "PB10_21") (pintype "bidirectional"))
    )
    (net (code "81") (name "unconnected-(U2-PB11-Pad22)") (class "Default")
      (node (ref "U2") (pin "22") (pinfunction "PB11_22") (pintype "bidirectional"))
    )
    (net (code "82") (name "unconnected-(U2-PB12-Pad25)") (class "Default")
      (node (ref "U2") (pin "25") (pinfunction "PB12_25") (pintype "bidirectional"))
    )
    (net (code "83") (name "unconnected-(U2-PC13-TAMPER-RTC-Pad2)") (class "Default")
      (node (ref "U2") (pin "2") (pinfunction "PC13-TAMPER-RTC_2") (pintype "bidirectional"))
    )
    (net (code "84") (name "unconnected-(U2-PC14-OSC32_IN-Pad3)") (class "Default")
      (node (ref "U2") (pin "3") (pinfunction "PC14-OSC32_IN_3") (pintype "bidirectional"))
    )
    (net (code "85") (name "unconnected-(U2-PC15-OSC32_OUT-Pad4)") (class "Default")
      (node (ref "U2") (pin "4") (pinfunction "PC15-OSC32_OUT_4") (pintype "bidirectional"))
    )
    (net (code "86") (name "unconnected-(U2-PD0-OSC_IN-Pad5)") (class "Default")
      (node (ref "U2") (pin "5") (pinfunction "PD0-OSC_IN_5") (pintype "input"))
    )
    (net (code "87") (name "unconnected-(U2-PD1-OSC_OUT-Pad6)") (class "Default")
      (node (ref "U2") (pin "6") (pinfunction "PD1-OSC_OUT_6") (pintype "output"))
    )
    (net (code "88") (name "unconnected-(X2A-KL-Pad1)") (class "Default")
      (node (ref "X2") (pin "1") (pinfunction "KL_1") (pintype "passive"))
    )
  )
)
